# Modulo_Ignicao_Enertron.net
KiCad netlist of a schematic drawn in EAGLE
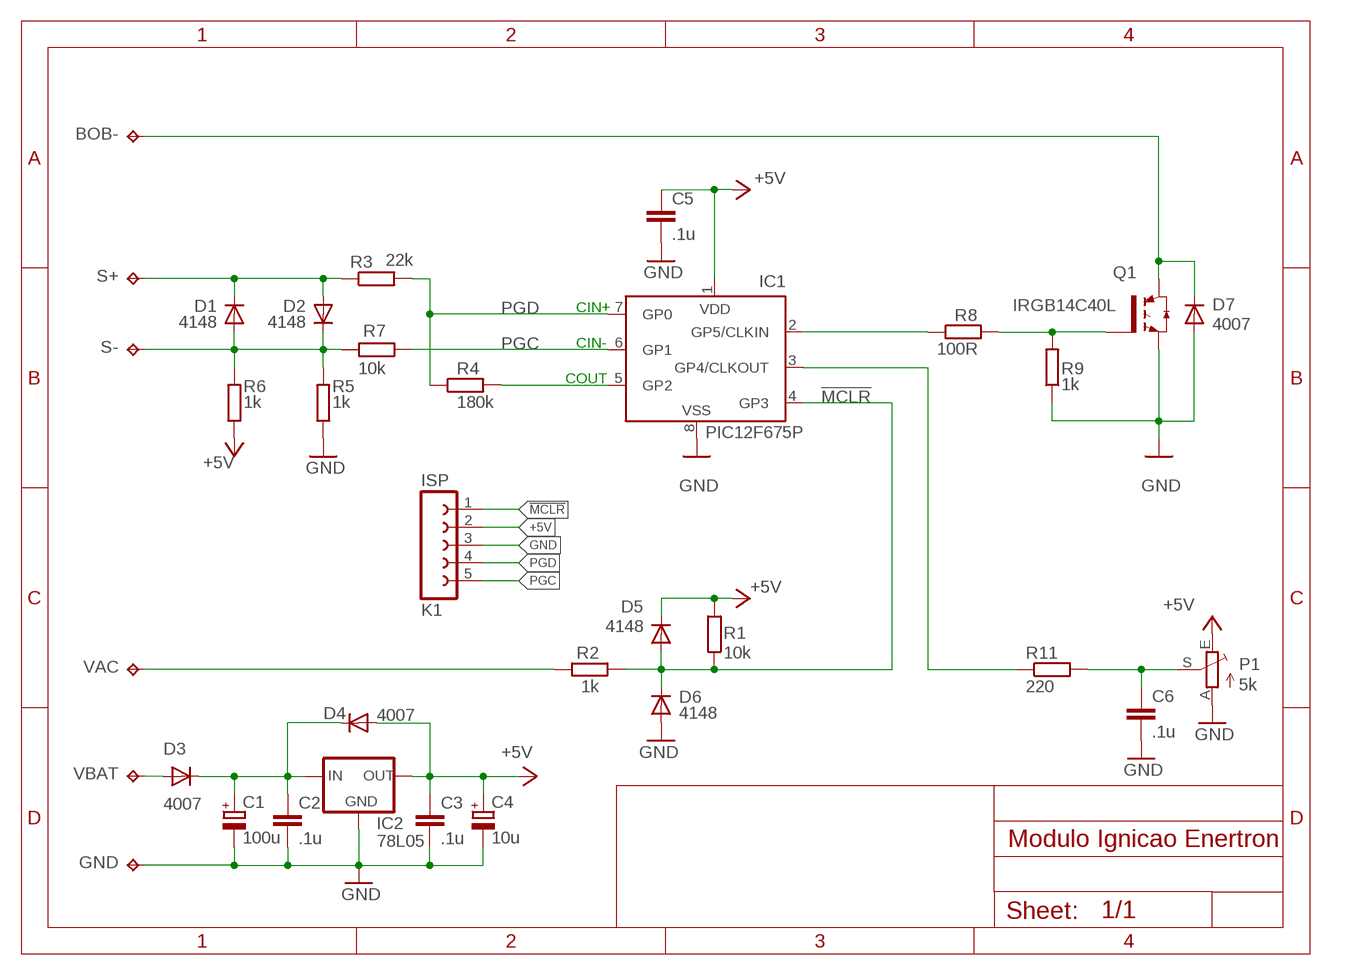
[diagram p0: schematic, sheet 1]

(export (version "E")
  (design (tool "Eeschema 10.0.6"))
  (components
    (comp (ref "BOB-")
      (value "TPPAD1-13Y")
      (footprint "eagle-import:P1-13Y")
      (libsource (lib "eagle-import") (part "TPPAD1-13Y"))
    )
    (comp (ref "C1")
      (value "100u")
      (footprint "eagle-import:E2,5-6")
      (libsource (lib "eagle-import") (part "CPOL-EUE2.5-6"))
    )
    (comp (ref "C2")
      (value ".1u")
      (footprint "eagle-import:C050-024X044")
      (libsource (lib "eagle-import") (part "C-EU050-024X044"))
    )
    (comp (ref "C3")
      (value ".1u")
      (footprint "eagle-import:C050-024X044")
      (libsource (lib "eagle-import") (part "C-EU050-024X044"))
    )
    (comp (ref "C4")
      (value "10u")
      (footprint "eagle-import:E2-4")
      (libsource (lib "eagle-import") (part "CPOL-EUE2-4"))
    )
    (comp (ref "C5")
      (value ".1u")
      (footprint "eagle-import:C050-024X044")
      (libsource (lib "eagle-import") (part "C-EU050-024X044"))
    )
    (comp (ref "C6")
      (value ".1u")
      (footprint "eagle-import:C050-024X044")
      (libsource (lib "eagle-import") (part "C-EU050-024X044"))
    )
    (comp (ref "D1")
      (value "4148")
      (footprint "eagle-import:D-5")
      (libsource (lib "eagle-import") (part "DIODE-D-5"))
    )
    (comp (ref "D2")
      (value "4148")
      (footprint "eagle-import:D-5")
      (libsource (lib "eagle-import") (part "DIODE-D-5"))
    )
    (comp (ref "D3")
      (value "4007")
      (footprint "eagle-import:D-7.5")
      (libsource (lib "eagle-import") (part "DIODE-D-7.5"))
    )
    (comp (ref "D4")
      (value "4007")
      (footprint "eagle-import:D-7.5")
      (libsource (lib "eagle-import") (part "DIODE-D-7.5"))
    )
    (comp (ref "D5")
      (value "4148")
      (footprint "eagle-import:D-5")
      (libsource (lib "eagle-import") (part "DIODE-D-5"))
    )
    (comp (ref "D6")
      (value "4148")
      (footprint "eagle-import:D-5")
      (libsource (lib "eagle-import") (part "DIODE-D-5"))
    )
    (comp (ref "D7")
      (value "4007")
      (footprint "eagle-import:D-7.5")
      (libsource (lib "eagle-import") (part "DIODE-D-7.5"))
    )
    (comp (ref "GND")
      (value "TPPAD1-13Y")
      (footprint "eagle-import:P1-13Y")
      (libsource (lib "eagle-import") (part "TPPAD1-13Y"))
    )
    (comp (ref "IC1")
      (value "PIC12F675P")
      (footprint "eagle-import:DIL8")
      (fields (field (name "MF") "MICROCHIP") (field (name "MPN") "PIC12F675-E/P"))
      (libsource (lib "eagle-import") (part "PIC12F6P75"))
    )
    (comp (ref "IC2")
      (value "78L05")
      (footprint "eagle-import:78LXX")
      (libsource (lib "eagle-import") (part "78LXX"))
    )
    (comp (ref "K1")
      (value "ISP")
      (footprint "eagle-import:FE05-1")
      (libsource (lib "eagle-import") (part "FE05-1"))
    )
    (comp (ref "P1")
      (value "5k")
      (footprint "eagle-import:CA6V")
      (libsource (lib "eagle-import") (part "TRIM_EU-CA6V"))
    )
    (comp (ref "Q1")
      (value "IRGB14C40L")
      (footprint "eagle-import:TO262-V")
      (libsource (lib "eagle-import") (part "IRG4BC15UD--L"))
    )
    (comp (ref "R1")
      (value "10k")
      (footprint "eagle-import:0204_7")
      (libsource (lib "eagle-import") (part "R-EU_0204/7"))
    )
    (comp (ref "R2")
      (value "1k")
      (footprint "eagle-import:0204_7")
      (libsource (lib "eagle-import") (part "R-EU_0204/7"))
    )
    (comp (ref "R3")
      (value "22k")
      (footprint "eagle-import:0204_7")
      (libsource (lib "eagle-import") (part "R-EU_0204/7"))
    )
    (comp (ref "R4")
      (value "180k")
      (footprint "eagle-import:0204_7")
      (libsource (lib "eagle-import") (part "R-EU_0204/7"))
    )
    (comp (ref "R5")
      (value "1k")
      (footprint "eagle-import:0204_7")
      (libsource (lib "eagle-import") (part "R-EU_0204/7"))
    )
    (comp (ref "R6")
      (value "1k")
      (footprint "eagle-import:0204_7")
      (libsource (lib "eagle-import") (part "R-EU_0204/7"))
    )
    (comp (ref "R7")
      (value "10k")
      (footprint "eagle-import:0204_7")
      (libsource (lib "eagle-import") (part "R-EU_0204/7"))
    )
    (comp (ref "R8")
      (value "100R")
      (footprint "eagle-import:0204_7")
      (libsource (lib "eagle-import") (part "R-EU_0204/7"))
    )
    (comp (ref "R9")
      (value "1k")
      (footprint "eagle-import:0204_7")
      (libsource (lib "eagle-import") (part "R-EU_0204/7"))
    )
    (comp (ref "R11")
      (value "220")
      (footprint "eagle-import:0204_7")
      (libsource (lib "eagle-import") (part "R-EU_0204/7"))
    )
    (comp (ref "S+")
      (value "TPPAD1-13Y")
      (footprint "eagle-import:P1-13Y")
      (libsource (lib "eagle-import") (part "TPPAD1-13Y"))
    )
    (comp (ref "S-")
      (value "TPPAD1-13Y")
      (footprint "eagle-import:P1-13Y")
      (libsource (lib "eagle-import") (part "TPPAD1-13Y"))
    )
    (comp (ref "VAC")
      (value "TPPAD1-13Y")
      (footprint "eagle-import:P1-13Y")
      (libsource (lib "eagle-import") (part "TPPAD1-13Y"))
    )
    (comp (ref "VBAT")
      (value "TPPAD1-13Y")
      (footprint "eagle-import:P1-13Y")
      (libsource (lib "eagle-import") (part "TPPAD1-13Y"))
    )
  )
  (nets
    (net (code "1") (name "+5V") (class "Default")
      (node (ref "C3") (pin "1") (pinfunction "1_1") (pintype "passive"))
      (node (ref "C4") (pin "+") (pinfunction "+_+") (pintype "passive"))
      (node (ref "C5") (pin "1") (pinfunction "1_1") (pintype "passive"))
      (node (ref "D4") (pin "A") (pinfunction "A_A") (pintype "passive"))
      (node (ref "D5") (pin "C") (pinfunction "C_C") (pintype "passive"))
      (node (ref "IC1") (pin "1") (pinfunction "VDD_1") (pintype "power_in"))
      (node (ref "IC2") (pin "OUT") (pinfunction "OUT_OUT") (pintype "passive"))
      (node (ref "K1") (pin "2") (pinfunction "2_2") (pintype "passive"))
      (node (ref "P1") (pin "E") (pinfunction "E_E") (pintype "passive"))
      (node (ref "R1") (pin "2") (pinfunction "2_2") (pintype "passive"))
      (node (ref "R6") (pin "1") (pinfunction "1_1") (pintype "passive"))
    )
    (net (code "2") (name "/~{MCLR}") (class "Default")
      (node (ref "D5") (pin "A") (pinfunction "A_A") (pintype "passive"))
      (node (ref "D6") (pin "C") (pinfunction "C_C") (pintype "passive"))
      (node (ref "IC1") (pin "4") (pinfunction "GP3_4") (pintype "input"))
      (node (ref "K1") (pin "1") (pinfunction "1_1") (pintype "passive"))
      (node (ref "R1") (pin "1") (pinfunction "1_1") (pintype "passive"))
      (node (ref "R2") (pin "1") (pinfunction "1_1") (pintype "passive"))
    )
    (net (code "3") (name "GND") (class "Default")
      (node (ref "C1") (pin "-") (pinfunction "-_-") (pintype "passive"))
      (node (ref "C2") (pin "2") (pinfunction "2_2") (pintype "passive"))
      (node (ref "C3") (pin "2") (pinfunction "2_2") (pintype "passive"))
      (node (ref "C4") (pin "-") (pinfunction "-_-") (pintype "passive"))
      (node (ref "C5") (pin "2") (pinfunction "2_2") (pintype "passive"))
      (node (ref "C6") (pin "2") (pinfunction "2_2") (pintype "passive"))
      (node (ref "D6") (pin "A") (pinfunction "A_A") (pintype "passive"))
      (node (ref "D7") (pin "A") (pinfunction "A_A") (pintype "passive"))
      (node (ref "GND") (pin "TP") (pinfunction "TP_TP") (pintype "input"))
      (node (ref "IC1") (pin "8") (pinfunction "VSS_8") (pintype "power_in"))
      (node (ref "IC2") (pin "GND") (pinfunction "GND_GND") (pintype "input"))
      (node (ref "K1") (pin "3") (pinfunction "3_3") (pintype "passive"))
      (node (ref "P1") (pin "A") (pinfunction "A_A") (pintype "passive"))
      (node (ref "Q1") (pin "3") (pinfunction "E_3") (pintype "passive"))
      (node (ref "R5") (pin "1") (pinfunction "1_1") (pintype "passive"))
      (node (ref "R9") (pin "1") (pinfunction "1_1") (pintype "passive"))
    )
    (net (code "4") (name "Net-(C1-Pad+)") (class "Default")
      (node (ref "C1") (pin "+") (pinfunction "+_+") (pintype "passive"))
      (node (ref "C2") (pin "1") (pinfunction "1_1") (pintype "passive"))
      (node (ref "D3") (pin "C") (pinfunction "C_C") (pintype "passive"))
      (node (ref "D4") (pin "C") (pinfunction "C_C") (pintype "passive"))
      (node (ref "IC2") (pin "IN") (pinfunction "IN_IN") (pintype "input"))
    )
    (net (code "5") (name "Net-(C6-Pad1)") (class "Default")
      (node (ref "C6") (pin "1") (pinfunction "1_1") (pintype "passive"))
      (node (ref "P1") (pin "S") (pinfunction "S_S") (pintype "passive"))
      (node (ref "R11") (pin "2") (pinfunction "2_2") (pintype "passive"))
    )
    (net (code "6") (name "Net-(D1-PadA)") (class "Default")
      (node (ref "D1") (pin "A") (pinfunction "A_A") (pintype "passive"))
      (node (ref "D2") (pin "C") (pinfunction "C_C") (pintype "passive"))
      (node (ref "R5") (pin "2") (pinfunction "2_2") (pintype "passive"))
      (node (ref "R6") (pin "2") (pinfunction "2_2") (pintype "passive"))
      (node (ref "R7") (pin "2") (pinfunction "2_2") (pintype "passive"))
      (node (ref "S-") (pin "TP") (pinfunction "TP_TP") (pintype "input"))
    )
    (net (code "7") (name "Net-(D1-PadC)") (class "Default")
      (node (ref "D1") (pin "C") (pinfunction "C_C") (pintype "passive"))
      (node (ref "D2") (pin "A") (pinfunction "A_A") (pintype "passive"))
      (node (ref "R3") (pin "1") (pinfunction "1_1") (pintype "passive"))
      (node (ref "S+") (pin "TP") (pinfunction "TP_TP") (pintype "input"))
    )
    (net (code "8") (name "Net-(D3-PadA)") (class "Default")
      (node (ref "D3") (pin "A") (pinfunction "A_A") (pintype "passive"))
      (node (ref "VBAT") (pin "TP") (pinfunction "TP_TP") (pintype "input"))
    )
    (net (code "9") (name "Net-(IC1-GP2)") (class "Default")
      (node (ref "IC1") (pin "5") (pinfunction "GP2_5") (pintype "bidirectional"))
      (node (ref "R4") (pin "2") (pinfunction "2_2") (pintype "passive"))
    )
    (net (code "10") (name "Net-(IC1-GP4{slash}CLKOUT)") (class "Default")
      (node (ref "IC1") (pin "3") (pinfunction "GP4/CLKOUT_3") (pintype "bidirectional"))
      (node (ref "R11") (pin "1") (pinfunction "1_1") (pintype "passive"))
    )
    (net (code "11") (name "Net-(IC1-GP5{slash}CLKIN)") (class "Default")
      (node (ref "IC1") (pin "2") (pinfunction "GP5/CLKIN_2") (pintype "bidirectional"))
      (node (ref "R8") (pin "1") (pinfunction "1_1") (pintype "passive"))
    )
    (net (code "12") (name "Net-(Q1-C)") (class "Default")
      (node (ref "BOB-") (pin "TP") (pinfunction "TP_TP") (pintype "input"))
      (node (ref "D7") (pin "C") (pinfunction "C_C") (pintype "passive"))
      (node (ref "Q1") (pin "2") (pinfunction "C_2") (pintype "passive"))
    )
    (net (code "13") (name "Net-(Q1-G)") (class "Default")
      (node (ref "Q1") (pin "1") (pinfunction "G_1") (pintype "passive"))
      (node (ref "R8") (pin "2") (pinfunction "2_2") (pintype "passive"))
      (node (ref "R9") (pin "2") (pinfunction "2_2") (pintype "passive"))
    )
    (net (code "14") (name "Net-(R2-Pad2)") (class "Default")
      (node (ref "R2") (pin "2") (pinfunction "2_2") (pintype "passive"))
      (node (ref "VAC") (pin "TP") (pinfunction "TP_TP") (pintype "input"))
    )
    (net (code "15") (name "PGC") (class "Default")
      (node (ref "IC1") (pin "6") (pinfunction "GP1_6") (pintype "bidirectional"))
      (node (ref "K1") (pin "5") (pinfunction "5_5") (pintype "passive"))
      (node (ref "R7") (pin "1") (pinfunction "1_1") (pintype "passive"))
    )
    (net (code "16") (name "PGD") (class "Default")
      (node (ref "IC1") (pin "7") (pinfunction "GP0_7") (pintype "bidirectional"))
      (node (ref "K1") (pin "4") (pinfunction "4_4") (pintype "passive"))
      (node (ref "R3") (pin "2") (pinfunction "2_2") (pintype "passive"))
      (node (ref "R4") (pin "1") (pinfunction "1_1") (pintype "passive"))
    )
  )
)
